# smd_can4vscp_rs232_rev_B.net
KiCad netlist of a schematic drawn in EAGLE
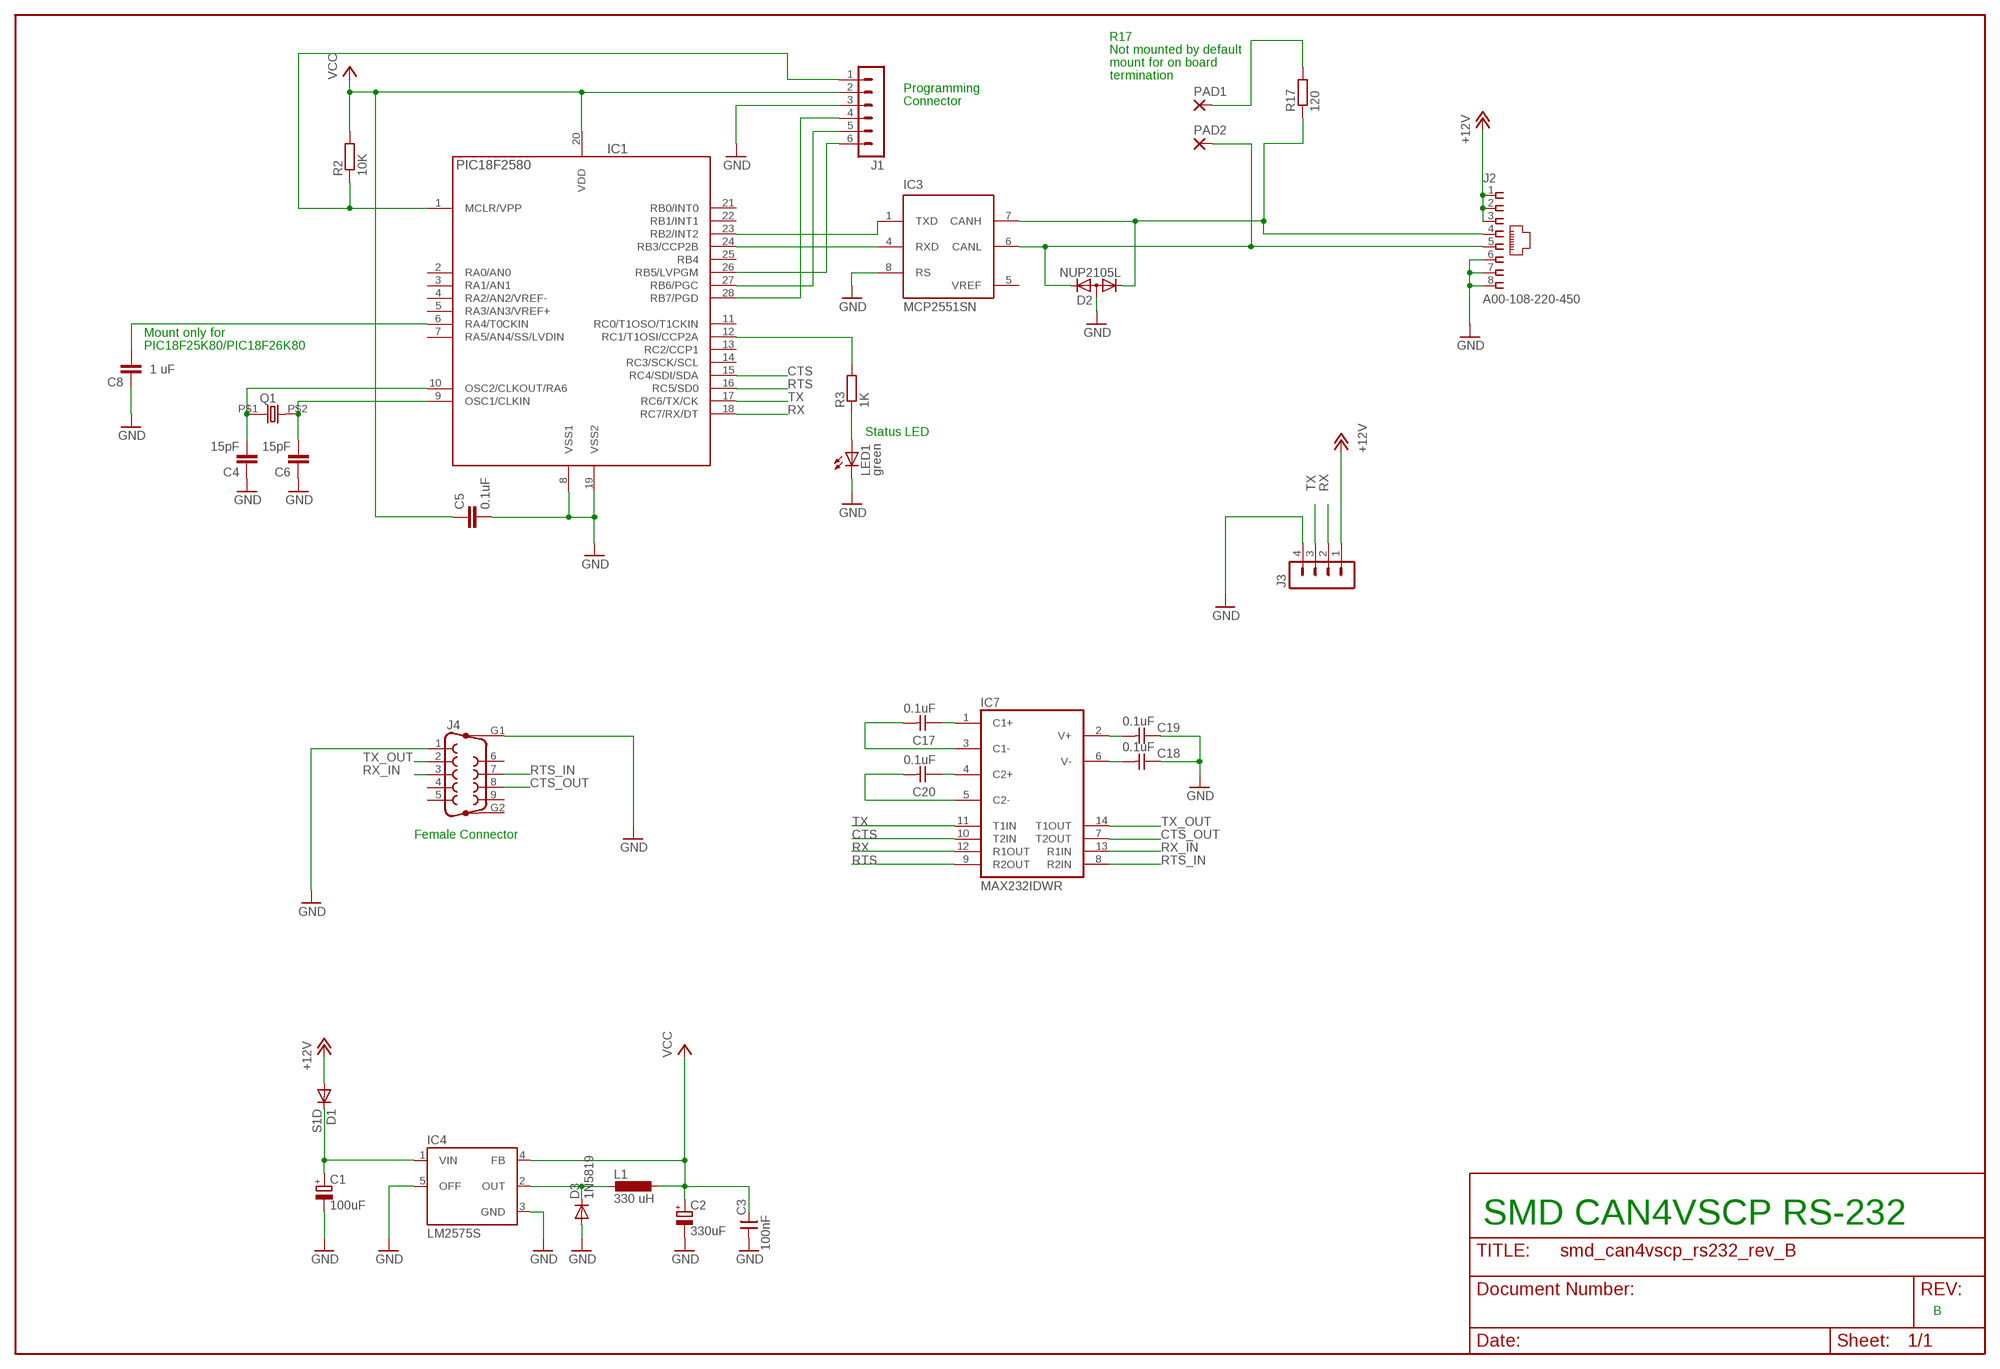
[diagram p0: schematic, sheet 1]

(export (version "E")
  (design (tool "Eeschema 10.0.6"))
  (components
    (comp (ref "C1")
      (value "100uF")
      (footprint "eagle-import:PANASONIC_D")
      (libsource (lib "eagle-import") (part "CPOL-EUD"))
    )
    (comp (ref "C2")
      (value "330uF")
      (footprint "eagle-import:PANASONIC_D")
      (libsource (lib "eagle-import") (part "CPOL-EUD"))
    )
    (comp (ref "C3")
      (value "100nF")
      (footprint "eagle-import:0805")
      (libsource (lib "eagle-import") (part "CNP-0805"))
    )
    (comp (ref "C4")
      (value "15pF")
      (footprint "eagle-import:C0805")
      (libsource (lib "eagle-import") (part "C-EUC0805"))
    )
    (comp (ref "C5")
      (value "0.1uF")
      (footprint "eagle-import:C0805")
      (libsource (lib "eagle-import") (part "C-EUC0805"))
    )
    (comp (ref "C6")
      (value "15pF")
      (footprint "eagle-import:C0805")
      (libsource (lib "eagle-import") (part "C-EUC0805"))
    )
    (comp (ref "C8")
      (value "1 uF")
      (footprint "eagle-import:C0805")
      (libsource (lib "eagle-import") (part "C-EUC0805"))
    )
    (comp (ref "C17")
      (value "0.1uF")
      (footprint "eagle-import:C0805")
      (libsource (lib "eagle-import") (part "NP_CAP0805"))
    )
    (comp (ref "C18")
      (value "0.1uF")
      (footprint "eagle-import:C0805")
      (libsource (lib "eagle-import") (part "NP_CAP0805"))
    )
    (comp (ref "C19")
      (value "0.1uF")
      (footprint "eagle-import:C0805")
      (libsource (lib "eagle-import") (part "NP_CAP0805"))
    )
    (comp (ref "C20")
      (value "0.1uF")
      (footprint "eagle-import:C0805")
      (libsource (lib "eagle-import") (part "NP_CAP0805"))
    )
    (comp (ref "D1")
      (value "S1D")
      (footprint "eagle-import:SOD123")
      (libsource (lib "eagle-import") (part "DIODE-SOD123"))
    )
    (comp (ref "D2")
      (value "NUP2105L")
      (footprint "eagle-import:SOT23")
      (libsource (lib "eagle-import") (part "DIODE-2CA|ACSOT23"))
    )
    (comp (ref "D3")
      (value "1N5819")
      (footprint "eagle-import:SOD123")
      (libsource (lib "eagle-import") (part "DIODE-SOD123"))
    )
    (comp (ref "IC1")
      (value "PIC18F2580")
      (footprint "eagle-import:SO28")
      (libsource (lib "eagle-import") (part "PIC18F252-?I/SOL"))
    )
    (comp (ref "IC3")
      (value "MCP2551SN")
      (footprint "eagle-import:SO-08")
      (libsource (lib "eagle-import") (part "MCP2551SN"))
    )
    (comp (ref "IC4")
      (value "LM2575S")
      (footprint "eagle-import:TO263-5")
      (libsource (lib "eagle-import") (part "LM2575S"))
    )
    (comp (ref "IC7")
      (value "MAX232IDWR")
      (footprint "eagle-import:SO16L")
      (libsource (lib "eagle-import") (part "MAX232ECWE"))
    )
    (comp (ref "J1")
      (value "MA06-1")
      (footprint "eagle-import:MA06-1")
      (libsource (lib "eagle-import") (part "MA06-1"))
    )
    (comp (ref "J2")
      (value "A00-108-220-450")
      (footprint "eagle-import:RJ-45")
      (libsource (lib "eagle-import") (part "A00-108-220-450"))
    )
    (comp (ref "J3")
      (value "MA04-1")
      (footprint "eagle-import:MA04-1")
      (libsource (lib "eagle-import") (part "MA04-1"))
    )
    (comp (ref "J4")
      (value "F09HP")
      (footprint "eagle-import:F09HP")
      (libsource (lib "eagle-import") (part "F09HP"))
    )
    (comp (ref "L1")
      (value "330 uH")
      (footprint "eagle-import:DO3316P")
      (libsource (lib "eagle-import") (part "DO3316P"))
    )
    (comp (ref "LED1")
      (value "green")
      (footprint "eagle-import:CHIPLED_0805")
      (libsource (lib "eagle-import") (part "LEDCHIPLED_0805"))
    )
    (comp (ref "PAD1")
      (value "1,6/0,8")
      (footprint "eagle-import:1,6_0,8")
      (libsource (lib "eagle-import") (part "1,6/0,8"))
    )
    (comp (ref "PAD2")
      (value "1,6/0,8")
      (footprint "eagle-import:1,6_0,8")
      (libsource (lib "eagle-import") (part "1,6/0,8"))
    )
    (comp (ref "Q1")
      (value "HC-49S")
      (footprint "eagle-import:9C")
      (libsource (lib "eagle-import") (part "HC-49S"))
    )
    (comp (ref "R2")
      (value "10K")
      (footprint "eagle-import:R0805")
      (libsource (lib "eagle-import") (part "R-EU_R0805"))
    )
    (comp (ref "R3")
      (value "1K")
      (footprint "eagle-import:R0805")
      (libsource (lib "eagle-import") (part "R-EU_R0805"))
    )
    (comp (ref "R17")
      (value "120")
      (footprint "eagle-import:R0805")
      (libsource (lib "eagle-import") (part "R-EU_R0805"))
    )
  )
  (nets
    (net (code "1") (name "+12V") (class "Default")
      (node (ref "D1") (pin "A") (pinfunction "A_A") (pintype "passive"))
      (node (ref "J2") (pin "1") (pinfunction "1_1") (pintype "passive"))
      (node (ref "J2") (pin "2") (pinfunction "2_2") (pintype "passive"))
      (node (ref "J2") (pin "3") (pinfunction "3_3") (pintype "passive"))
      (node (ref "J3") (pin "1") (pinfunction "1_1") (pintype "passive"))
    )
    (net (code "2") (name "/CTS") (class "Default")
      (node (ref "IC1") (pin "15") (pinfunction "RC4/SDI/SDA_15") (pintype "bidirectional"))
      (node (ref "IC7") (pin "10") (pinfunction "T2IN_10") (pintype "input"))
    )
    (net (code "3") (name "/CTS_OUT") (class "Default")
      (node (ref "IC7") (pin "7") (pinfunction "T2OUT_7") (pintype "output"))
      (node (ref "J4") (pin "8") (pinfunction "8_8") (pintype "passive"))
    )
    (net (code "4") (name "/RTS") (class "Default")
      (node (ref "IC1") (pin "16") (pinfunction "RC5/SD0_16") (pintype "bidirectional"))
      (node (ref "IC7") (pin "9") (pinfunction "R2OUT_9") (pintype "output"))
    )
    (net (code "5") (name "/RTS_IN") (class "Default")
      (node (ref "IC7") (pin "8") (pinfunction "R2IN_8") (pintype "input"))
      (node (ref "J4") (pin "7") (pinfunction "7_7") (pintype "passive"))
    )
    (net (code "6") (name "/RX") (class "Default")
      (node (ref "IC1") (pin "18") (pinfunction "RC7/RX/DT_18") (pintype "bidirectional"))
      (node (ref "IC7") (pin "12") (pinfunction "R1OUT_12") (pintype "output"))
      (node (ref "J3") (pin "2") (pinfunction "2_2") (pintype "passive"))
    )
    (net (code "7") (name "/RX_IN") (class "Default")
      (node (ref "IC7") (pin "13") (pinfunction "R1IN_13") (pintype "input"))
      (node (ref "J4") (pin "3") (pinfunction "3_3") (pintype "passive"))
    )
    (net (code "8") (name "/TX") (class "Default")
      (node (ref "IC1") (pin "17") (pinfunction "RC6/TX/CK_17") (pintype "bidirectional"))
      (node (ref "IC7") (pin "11") (pinfunction "T1IN_11") (pintype "input"))
      (node (ref "J3") (pin "3") (pinfunction "3_3") (pintype "passive"))
    )
    (net (code "9") (name "/TX_OUT") (class "Default")
      (node (ref "IC7") (pin "14") (pinfunction "T1OUT_14") (pintype "output"))
      (node (ref "J4") (pin "2") (pinfunction "2_2") (pintype "passive"))
    )
    (net (code "10") (name "/VREF") (class "Default")
      (node (ref "IC3") (pin "5") (pinfunction "VREF_5") (pintype "power_in"))
    )
    (net (code "11") (name "GND") (class "Default")
      (node (ref "C1") (pin "-") (pinfunction "-_-") (pintype "passive"))
      (node (ref "C18") (pin "1") (pinfunction "1_1") (pintype "passive"))
      (node (ref "C19") (pin "1") (pinfunction "1_1") (pintype "passive"))
      (node (ref "C2") (pin "-") (pinfunction "-_-") (pintype "passive"))
      (node (ref "C3") (pin "1") (pinfunction "1_1") (pintype "passive"))
      (node (ref "C4") (pin "1") (pinfunction "1_1") (pintype "passive"))
      (node (ref "C5") (pin "2") (pinfunction "2_2") (pintype "passive"))
      (node (ref "C6") (pin "1") (pinfunction "1_1") (pintype "passive"))
      (node (ref "C8") (pin "1") (pinfunction "1_1") (pintype "passive"))
      (node (ref "D2") (pin "3") (pinfunction "A_3") (pintype "passive"))
      (node (ref "D3") (pin "A") (pinfunction "A_A") (pintype "passive"))
      (node (ref "IC1") (pin "19") (pinfunction "VSS2_19") (pintype "power_in"))
      (node (ref "IC1") (pin "8") (pinfunction "VSS1_8") (pintype "power_in"))
      (node (ref "IC3") (pin "8") (pinfunction "RS_8") (pintype "input"))
      (node (ref "IC4") (pin "3") (pinfunction "GND_3") (pintype "power_in"))
      (node (ref "IC4") (pin "5") (pinfunction "OFF_5") (pintype "input"))
      (node (ref "J1") (pin "3") (pinfunction "3_3") (pintype "passive"))
      (node (ref "J2") (pin "6") (pinfunction "6_6") (pintype "passive"))
      (node (ref "J2") (pin "7") (pinfunction "7_7") (pintype "passive"))
      (node (ref "J2") (pin "8") (pinfunction "8_8") (pintype "passive"))
      (node (ref "J3") (pin "4") (pinfunction "4_4") (pintype "passive"))
      (node (ref "J4") (pin "1") (pinfunction "1_1") (pintype "passive"))
      (node (ref "J4") (pin "G1") (pinfunction "G1_G1") (pintype "passive"))
      (node (ref "LED1") (pin "C") (pinfunction "C_C") (pintype "passive"))
    )
    (net (code "12") (name "Net-(D2-K1)") (class "Default")
      (node (ref "D2") (pin "1") (pinfunction "K1_1") (pintype "passive"))
      (node (ref "IC3") (pin "7") (pinfunction "CANH_7") (pintype "bidirectional"))
      (node (ref "J2") (pin "4") (pinfunction "4_4") (pintype "passive"))
      (node (ref "R17") (pin "1") (pinfunction "1_1") (pintype "passive"))
    )
    (net (code "13") (name "Net-(D2-K2)") (class "Default")
      (node (ref "D2") (pin "2") (pinfunction "K2_2") (pintype "passive"))
      (node (ref "IC3") (pin "6") (pinfunction "CANL_6") (pintype "bidirectional"))
      (node (ref "J2") (pin "5") (pinfunction "5_5") (pintype "passive"))
      (node (ref "PAD2") (pin "1") (pinfunction "P_1") (pintype "passive"))
    )
    (net (code "14") (name "Net-(IC1-MCLR{slash}VPP)") (class "Default")
      (node (ref "IC1") (pin "1") (pinfunction "MCLR/VPP_1") (pintype "input"))
      (node (ref "J1") (pin "1") (pinfunction "1_1") (pintype "passive"))
      (node (ref "R2") (pin "1") (pinfunction "1_1") (pintype "passive"))
    )
    (net (code "15") (name "Net-(IC1-OSC1{slash}CLKIN)") (class "Default")
      (node (ref "C6") (pin "2") (pinfunction "2_2") (pintype "passive"))
      (node (ref "IC1") (pin "9") (pinfunction "OSC1/CLKIN_9") (pintype "input"))
      (node (ref "Q1") (pin "P$2") (pinfunction "2_P$2") (pintype "passive"))
    )
    (net (code "16") (name "Net-(IC1-OSC2{slash}CLKOUT{slash}RA6)") (class "Default")
      (node (ref "C4") (pin "2") (pinfunction "2_2") (pintype "passive"))
      (node (ref "IC1") (pin "10") (pinfunction "OSC2/CLKOUT/RA6_10") (pintype "output"))
      (node (ref "Q1") (pin "P$1") (pinfunction "1_P$1") (pintype "passive"))
    )
    (net (code "17") (name "Net-(IC1-RA4{slash}T0CKIN)") (class "Default")
      (node (ref "C8") (pin "2") (pinfunction "2_2") (pintype "passive"))
      (node (ref "IC1") (pin "6") (pinfunction "RA4/T0CKIN_6") (pintype "open_collector"))
    )
    (net (code "18") (name "Net-(IC1-RB2{slash}INT2)") (class "Default")
      (node (ref "IC1") (pin "23") (pinfunction "RB2/INT2_23") (pintype "bidirectional"))
      (node (ref "IC3") (pin "1") (pinfunction "TXD_1") (pintype "input"))
    )
    (net (code "19") (name "Net-(IC1-RB3{slash}CCP2B)") (class "Default")
      (node (ref "IC1") (pin "24") (pinfunction "RB3/CCP2B_24") (pintype "bidirectional"))
      (node (ref "IC3") (pin "4") (pinfunction "RXD_4") (pintype "output"))
    )
    (net (code "20") (name "Net-(IC1-RB5{slash}LVPGM)") (class "Default")
      (node (ref "IC1") (pin "26") (pinfunction "RB5/LVPGM_26") (pintype "bidirectional"))
      (node (ref "J1") (pin "6") (pinfunction "6_6") (pintype "passive"))
    )
    (net (code "21") (name "Net-(IC1-RB6{slash}PGC)") (class "Default")
      (node (ref "IC1") (pin "27") (pinfunction "RB6/PGC_27") (pintype "bidirectional"))
      (node (ref "J1") (pin "5") (pinfunction "5_5") (pintype "passive"))
    )
    (net (code "22") (name "Net-(IC1-RB7{slash}PGD)") (class "Default")
      (node (ref "IC1") (pin "28") (pinfunction "RB7/PGD_28") (pintype "bidirectional"))
      (node (ref "J1") (pin "4") (pinfunction "4_4") (pintype "passive"))
    )
    (net (code "23") (name "Net-(IC1-RC1{slash}T1OSI{slash}CCP2A)") (class "Default")
      (node (ref "IC1") (pin "12") (pinfunction "RC1/T1OSI/CCP2A_12") (pintype "bidirectional"))
      (node (ref "R3") (pin "2") (pinfunction "2_2") (pintype "passive"))
    )
    (net (code "24") (name "Net-(IC4-OUT)") (class "Default")
      (node (ref "D3") (pin "C") (pinfunction "C_C") (pintype "passive"))
      (node (ref "IC4") (pin "2") (pinfunction "OUT_2") (pintype "output"))
      (node (ref "L1") (pin "1") (pinfunction "1_1") (pintype "passive"))
    )
    (net (code "25") (name "Net-(IC4-VIN)") (class "Default")
      (node (ref "C1") (pin "+") (pinfunction "+_+") (pintype "passive"))
      (node (ref "D1") (pin "C") (pinfunction "C_C") (pintype "passive"))
      (node (ref "IC4") (pin "1") (pinfunction "VIN_1") (pintype "power_in"))
    )
    (net (code "26") (name "Net-(IC7A-C1+)") (class "Default")
      (node (ref "C17") (pin "1") (pinfunction "1_1") (pintype "passive"))
      (node (ref "IC7") (pin "1") (pinfunction "C1+_1") (pintype "bidirectional"))
    )
    (net (code "27") (name "Net-(IC7A-C1-)") (class "Default")
      (node (ref "C17") (pin "2") (pinfunction "2_2") (pintype "passive"))
      (node (ref "IC7") (pin "3") (pinfunction "C1-_3") (pintype "bidirectional"))
    )
    (net (code "28") (name "Net-(IC7A-C2+)") (class "Default")
      (node (ref "C20") (pin "1") (pinfunction "1_1") (pintype "passive"))
      (node (ref "IC7") (pin "4") (pinfunction "C2+_4") (pintype "bidirectional"))
    )
    (net (code "29") (name "Net-(IC7A-C2-)") (class "Default")
      (node (ref "C20") (pin "2") (pinfunction "2_2") (pintype "passive"))
      (node (ref "IC7") (pin "5") (pinfunction "C2-_5") (pintype "bidirectional"))
    )
    (net (code "30") (name "Net-(IC7A-V+)") (class "Default")
      (node (ref "C19") (pin "2") (pinfunction "2_2") (pintype "passive"))
      (node (ref "IC7") (pin "2") (pinfunction "V+_2") (pintype "bidirectional"))
    )
    (net (code "31") (name "Net-(IC7A-V-)") (class "Default")
      (node (ref "C18") (pin "2") (pinfunction "2_2") (pintype "passive"))
      (node (ref "IC7") (pin "6") (pinfunction "V-_6") (pintype "bidirectional"))
    )
    (net (code "32") (name "Net-(LED1-PadA)") (class "Default")
      (node (ref "LED1") (pin "A") (pinfunction "A_A") (pintype "passive"))
      (node (ref "R3") (pin "1") (pinfunction "1_1") (pintype "passive"))
    )
    (net (code "33") (name "Net-(PAD1-P)") (class "Default")
      (node (ref "PAD1") (pin "1") (pinfunction "P_1") (pintype "passive"))
      (node (ref "R17") (pin "2") (pinfunction "2_2") (pintype "passive"))
    )
    (net (code "34") (name "VCC") (class "Default")
      (node (ref "C2") (pin "+") (pinfunction "+_+") (pintype "passive"))
      (node (ref "C3") (pin "2") (pinfunction "2_2") (pintype "passive"))
      (node (ref "C5") (pin "1") (pinfunction "1_1") (pintype "passive"))
      (node (ref "IC1") (pin "20") (pinfunction "VDD_20") (pintype "power_in"))
      (node (ref "IC4") (pin "4") (pinfunction "FB_4") (pintype "input"))
      (node (ref "J1") (pin "2") (pinfunction "2_2") (pintype "passive"))
      (node (ref "L1") (pin "2") (pinfunction "2_2") (pintype "passive"))
      (node (ref "R2") (pin "2") (pinfunction "2_2") (pintype "passive"))
    )
    (net (code "35") (name "unconnected-(IC1-RA0{slash}AN0-Pad2)") (class "Default")
      (node (ref "IC1") (pin "2") (pinfunction "RA0/AN0_2") (pintype "bidirectional"))
    )
    (net (code "36") (name "unconnected-(IC1-RA1{slash}AN1-Pad3)") (class "Default")
      (node (ref "IC1") (pin "3") (pinfunction "RA1/AN1_3") (pintype "bidirectional"))
    )
    (net (code "37") (name "unconnected-(IC1-RA2{slash}AN2{slash}VREF--Pad4)") (class "Default")
      (node (ref "IC1") (pin "4") (pinfunction "RA2/AN2/VREF-_4") (pintype "bidirectional"))
    )
    (net (code "38") (name "unconnected-(IC1-RA3{slash}AN3{slash}VREF+-Pad5)") (class "Default")
      (node (ref "IC1") (pin "5") (pinfunction "RA3/AN3/VREF+_5") (pintype "bidirectional"))
    )
    (net (code "39") (name "unconnected-(IC1-RA5{slash}AN4{slash}SS{slash}LVDIN-Pad7)") (class "Default")
      (node (ref "IC1") (pin "7") (pinfunction "RA5/AN4/SS/LVDIN_7") (pintype "bidirectional"))
    )
    (net (code "40") (name "unconnected-(IC1-RB0{slash}INT0-Pad21)") (class "Default")
      (node (ref "IC1") (pin "21") (pinfunction "RB0/INT0_21") (pintype "bidirectional"))
    )
    (net (code "41") (name "unconnected-(IC1-RB1{slash}INT1-Pad22)") (class "Default")
      (node (ref "IC1") (pin "22") (pinfunction "RB1/INT1_22") (pintype "bidirectional"))
    )
    (net (code "42") (name "unconnected-(IC1-RB4-Pad25)") (class "Default")
      (node (ref "IC1") (pin "25") (pinfunction "RB4_25") (pintype "bidirectional"))
    )
    (net (code "43") (name "unconnected-(IC1-RC0{slash}T1OSO{slash}T1CKIN-Pad11)") (class "Default")
      (node (ref "IC1") (pin "11") (pinfunction "RC0/T1OSO/T1CKIN_11") (pintype "bidirectional"))
    )
    (net (code "44") (name "unconnected-(IC1-RC2{slash}CCP1-Pad13)") (class "Default")
      (node (ref "IC1") (pin "13") (pinfunction "RC2/CCP1_13") (pintype "bidirectional"))
    )
    (net (code "45") (name "unconnected-(IC1-RC3{slash}SCK{slash}SCL-Pad14)") (class "Default")
      (node (ref "IC1") (pin "14") (pinfunction "RC3/SCK/SCL_14") (pintype "bidirectional"))
    )
    (net (code "46") (name "unconnected-(J4-Pad4)") (class "Default")
      (node (ref "J4") (pin "4") (pinfunction "4_4") (pintype "passive"))
    )
    (net (code "47") (name "unconnected-(J4-Pad5)") (class "Default")
      (node (ref "J4") (pin "5") (pinfunction "5_5") (pintype "passive"))
    )
    (net (code "48") (name "unconnected-(J4-Pad6)") (class "Default")
      (node (ref "J4") (pin "6") (pinfunction "6_6") (pintype "passive"))
    )
    (net (code "49") (name "unconnected-(J4-Pad9)") (class "Default")
      (node (ref "J4") (pin "9") (pinfunction "9_9") (pintype "passive"))
    )
    (net (code "50") (name "unconnected-(J4-PadG2)") (class "Default")
      (node (ref "J4") (pin "G2") (pinfunction "G2_G2") (pintype "passive"))
    )
  )
)
